# MCU.net
KiCad netlist of a schematic drawn in Altium Designer
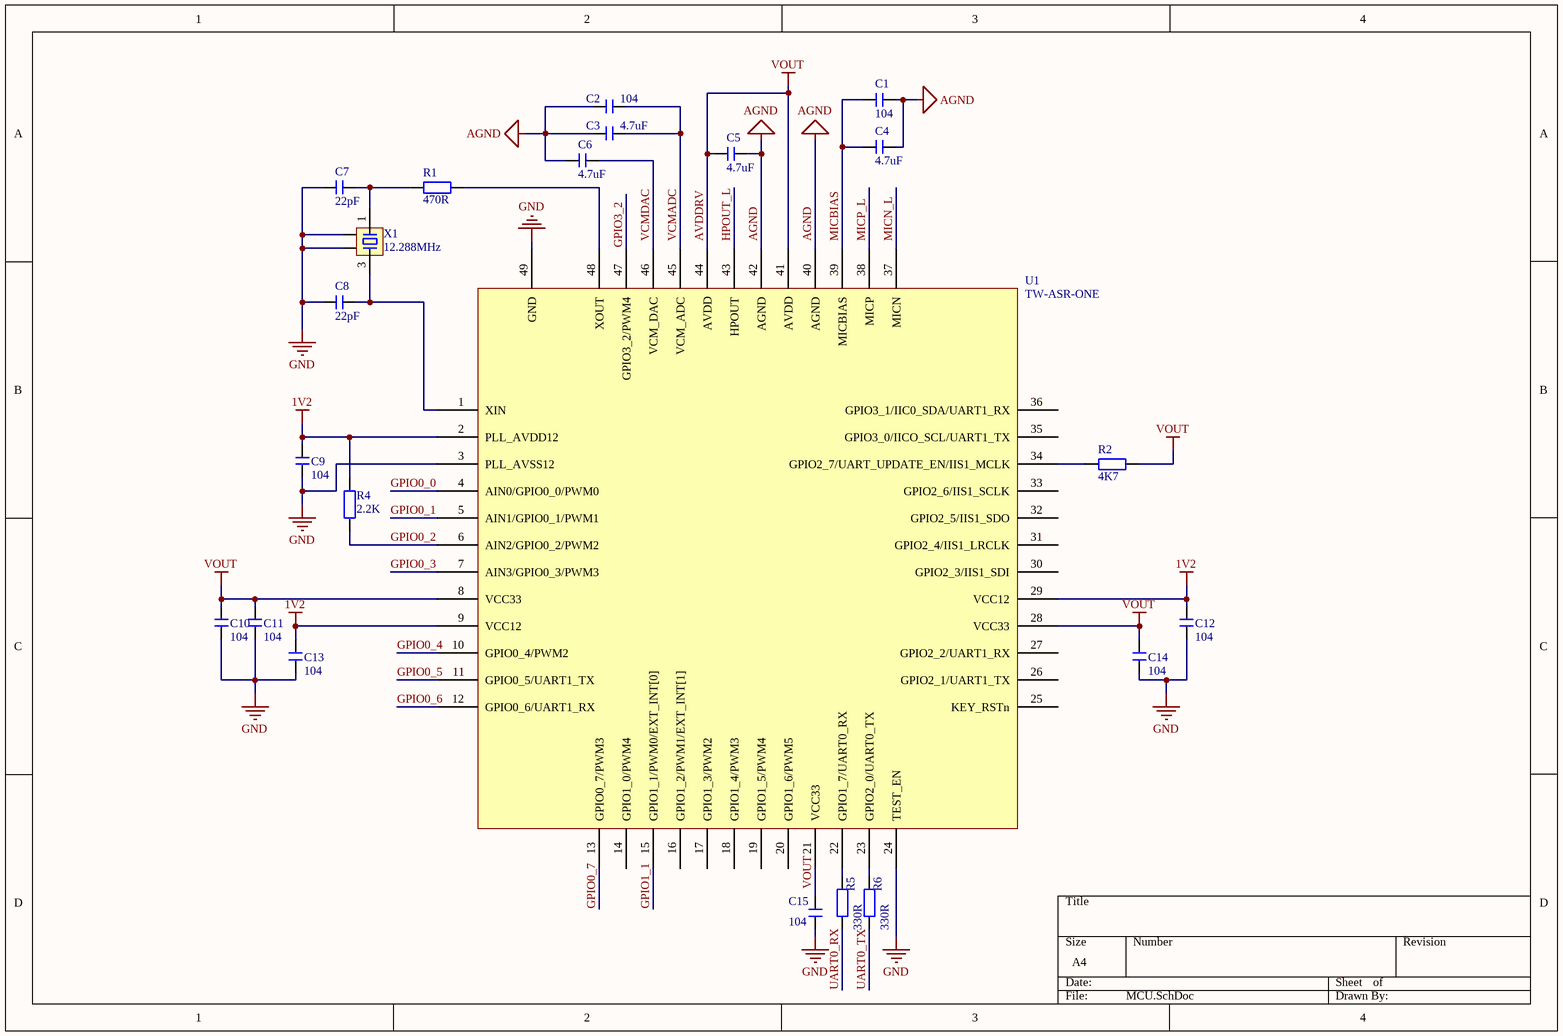
[diagram p0: MCU.SchDoc]

(export (version "E")
  (design (tool "Eeschema 10.0.6"))
  (components
    (comp (ref "C1")
      (value "104")
      (footprint "C 0603_L")
      (description "无极性贴片电容")
      (fields (field (name "版权归属") "源创客"))
      (libsource (lib "3.1   - 电阻-电容-电感") (part "C"))
    )
    (comp (ref "C2")
      (value "104")
      (footprint "C 0603_L")
      (description "无极性贴片电容")
      (fields (field (name "版权归属") "源创客"))
      (libsource (lib "3.1   - 电阻-电容-电感") (part "C"))
    )
    (comp (ref "C3")
      (value "4.7uF")
      (footprint "C 0603_L")
      (description "无极性贴片电容")
      (fields (field (name "版权归属") "源创客"))
      (libsource (lib "3.1   - 电阻-电容-电感") (part "C"))
    )
    (comp (ref "C4")
      (value "4.7uF")
      (footprint "C 0603_L")
      (description "无极性贴片电容")
      (fields (field (name "版权归属") "源创客"))
      (libsource (lib "3.1   - 电阻-电容-电感") (part "C"))
    )
    (comp (ref "C5")
      (value "4.7uF")
      (footprint "C 0603_L")
      (description "无极性贴片电容")
      (fields (field (name "版权归属") "源创客"))
      (libsource (lib "3.1   - 电阻-电容-电感") (part "C"))
    )
    (comp (ref "C6")
      (value "4.7uF")
      (footprint "C 0603_L")
      (description "无极性贴片电容")
      (fields (field (name "版权归属") "源创客"))
      (libsource (lib "3.1   - 电阻-电容-电感") (part "C"))
    )
    (comp (ref "C7")
      (value "22pF")
      (footprint "C 0603_L")
      (description "无极性贴片电容")
      (fields (field (name "版权归属") "源创客"))
      (libsource (lib "3.1   - 电阻-电容-电感") (part "C"))
    )
    (comp (ref "C8")
      (value "22pF")
      (footprint "C 0603_L")
      (description "无极性贴片电容")
      (fields (field (name "版权归属") "源创客"))
      (libsource (lib "3.1   - 电阻-电容-电感") (part "C"))
    )
    (comp (ref "C9")
      (value "104")
      (footprint "C 0603_L")
      (description "无极性贴片电容")
      (fields (field (name "版权归属") "源创客"))
      (libsource (lib "3.1   - 电阻-电容-电感") (part "C"))
    )
    (comp (ref "C10")
      (value "104")
      (footprint "C 0603_L")
      (description "无极性贴片电容")
      (fields (field (name "版权归属") "源创客"))
      (libsource (lib "3.1   - 电阻-电容-电感") (part "C"))
    )
    (comp (ref "C11")
      (value "104")
      (footprint "C 0603_L")
      (description "无极性贴片电容")
      (fields (field (name "版权归属") "源创客"))
      (libsource (lib "3.1   - 电阻-电容-电感") (part "C"))
    )
    (comp (ref "C12")
      (value "104")
      (footprint "C 0603_L")
      (description "无极性贴片电容")
      (fields (field (name "版权归属") "源创客"))
      (libsource (lib "3.1   - 电阻-电容-电感") (part "C"))
    )
    (comp (ref "C13")
      (value "104")
      (footprint "C 0603_L")
      (description "无极性贴片电容")
      (fields (field (name "版权归属") "源创客"))
      (libsource (lib "3.1   - 电阻-电容-电感") (part "C"))
    )
    (comp (ref "C14")
      (value "104")
      (footprint "C 0603_L")
      (description "无极性贴片电容")
      (fields (field (name "版权归属") "源创客"))
      (libsource (lib "3.1   - 电阻-电容-电感") (part "C"))
    )
    (comp (ref "C15")
      (value "104")
      (footprint "C 0603_L")
      (description "无极性贴片电容")
      (fields (field (name "版权归属") "源创客"))
      (libsource (lib "3.1   - 电阻-电容-电感") (part "C"))
    )
    (comp (ref "R1")
      (value "470R")
      (footprint "R 0603_L")
      (description "贴片电阻")
      (fields (field (name "版权归属") "源创客"))
      (libsource (lib "3.1   - 电阻-电容-电感") (part "R"))
    )
    (comp (ref "R2")
      (value "4K7")
      (footprint "R 0603_L")
      (description "贴片电阻")
      (fields (field (name "版权归属") "源创客"))
      (libsource (lib "3.1   - 电阻-电容-电感") (part "R"))
    )
    (comp (ref "R4")
      (value "2.2K")
      (footprint "R 0603_L")
      (description "贴片电阻")
      (fields (field (name "版权归属") "源创客"))
      (libsource (lib "3.1   - 电阻-电容-电感") (part "R"))
    )
    (comp (ref "R5")
      (value "330R")
      (footprint "R 0603_L")
      (description "贴片电阻")
      (fields (field (name "版权归属") "源创客"))
      (libsource (lib "3.1   - 电阻-电容-电感") (part "R"))
    )
    (comp (ref "R6")
      (value "330R")
      (footprint "R 0603_L")
      (description "贴片电阻")
      (fields (field (name "版权归属") "源创客"))
      (libsource (lib "3.1   - 电阻-电容-电感") (part "R"))
    )
    (comp (ref "U1")
      (value "TW-ASR-ONE")
      (footprint "QFN48 6X6")
      (libsource (lib "语音识别和合成模块") (part "TW-ASR-ONE"))
    )
    (comp (ref "X1")
      (value "12.288MHz")
      (footprint "OSC 3225-4P")
      (description "4脚无源晶振")
      (fields (field (name "版权归属") "源创客"))
      (libsource (lib "10.1 - 保险丝-晶振") (part "XTAL-4P"))
    )
  )
  (nets
    (net (code "1") (name "/GPIO0_0") (class "Default")
      (node (ref "U1") (pin "4") (pinfunction "AIN0/GPIO0_0/PWM0_4") (pintype "passive"))
    )
    (net (code "2") (name "/GPIO0_1") (class "Default")
      (node (ref "U1") (pin "5") (pinfunction "AIN1/GPIO0_1/PWM1_5") (pintype "passive"))
    )
    (net (code "3") (name "/GPIO0_2") (class "Default")
      (node (ref "R4") (pin "1") (pinfunction "1_1") (pintype "passive"))
      (node (ref "U1") (pin "6") (pinfunction "AIN2/GPIO0_2/PWM2_6") (pintype "passive"))
    )
    (net (code "4") (name "/GPIO0_3") (class "Default")
      (node (ref "U1") (pin "7") (pinfunction "AIN3/GPIO0_3/PWM3_7") (pintype "passive"))
    )
    (net (code "5") (name "/GPIO0_4") (class "Default")
      (node (ref "U1") (pin "10") (pinfunction "GPIO0_4/PWM2_10") (pintype "passive"))
    )
    (net (code "6") (name "/GPIO0_5") (class "Default")
      (node (ref "U1") (pin "11") (pinfunction "GPIO0_5/UART1_TX_11") (pintype "passive"))
    )
    (net (code "7") (name "/GPIO0_6") (class "Default")
      (node (ref "U1") (pin "12") (pinfunction "GPIO0_6/UART1_RX_12") (pintype "passive"))
    )
    (net (code "8") (name "/GPIO0_7") (class "Default")
      (node (ref "U1") (pin "13") (pinfunction "GPIO0_7/PWM3_13") (pintype "passive"))
    )
    (net (code "9") (name "/GPIO1_1") (class "Default")
      (node (ref "U1") (pin "15") (pinfunction "GPIO1_1/PWM0/EXT_INT[0]_15") (pintype "passive"))
    )
    (net (code "10") (name "/GPIO3_2") (class "Default")
      (node (ref "U1") (pin "47") (pinfunction "GPIO3_2/PWM4_47") (pintype "passive"))
    )
    (net (code "11") (name "/HPOUT_L") (class "Default")
      (node (ref "U1") (pin "43") (pinfunction "HPOUT_43") (pintype "passive"))
    )
    (net (code "12") (name "/MICBIAS") (class "Default")
      (node (ref "C1") (pin "1") (pinfunction "1_1") (pintype "passive"))
      (node (ref "C4") (pin "1") (pinfunction "1_1") (pintype "passive"))
      (node (ref "U1") (pin "39") (pinfunction "MICBIAS_39") (pintype "passive"))
    )
    (net (code "13") (name "/MICN_L") (class "Default")
      (node (ref "U1") (pin "37") (pinfunction "MICN_37") (pintype "passive"))
    )
    (net (code "14") (name "/MICP_L") (class "Default")
      (node (ref "U1") (pin "38") (pinfunction "MICP_38") (pintype "passive"))
    )
    (net (code "15") (name "/UART0_RX") (class "Default")
      (node (ref "R5") (pin "1") (pinfunction "1_1") (pintype "passive"))
    )
    (net (code "16") (name "/UART0_TX") (class "Default")
      (node (ref "R6") (pin "1") (pinfunction "1_1") (pintype "passive"))
    )
    (net (code "17") (name "/VCMADC") (class "Default")
      (node (ref "C2") (pin "2") (pinfunction "2_2") (pintype "passive"))
      (node (ref "C3") (pin "2") (pinfunction "2_2") (pintype "passive"))
      (node (ref "U1") (pin "45") (pinfunction "VCM_ADC_45") (pintype "passive"))
    )
    (net (code "18") (name "/VCMDAC") (class "Default")
      (node (ref "C6") (pin "2") (pinfunction "2_2") (pintype "passive"))
      (node (ref "U1") (pin "46") (pinfunction "VCM_DAC_46") (pintype "passive"))
    )
    (net (code "19") (name "1V2") (class "Default")
      (node (ref "C12") (pin "2") (pinfunction "2_2") (pintype "passive"))
      (node (ref "C13") (pin "2") (pinfunction "2_2") (pintype "passive"))
      (node (ref "C9") (pin "2") (pinfunction "2_2") (pintype "passive"))
      (node (ref "R4") (pin "2") (pinfunction "2_2") (pintype "passive"))
      (node (ref "U1") (pin "2") (pinfunction "PLL_AVDD12_2") (pintype "passive"))
      (node (ref "U1") (pin "29") (pinfunction "VCC12_29") (pintype "passive"))
      (node (ref "U1") (pin "9") (pinfunction "VCC12_9") (pintype "passive"))
    )
    (net (code "20") (name "AGND") (class "Default")
      (node (ref "C1") (pin "2") (pinfunction "2_2") (pintype "passive"))
      (node (ref "C2") (pin "1") (pinfunction "1_1") (pintype "passive"))
      (node (ref "C3") (pin "1") (pinfunction "1_1") (pintype "passive"))
      (node (ref "C4") (pin "2") (pinfunction "2_2") (pintype "passive"))
      (node (ref "C5") (pin "2") (pinfunction "2_2") (pintype "passive"))
      (node (ref "C6") (pin "1") (pinfunction "1_1") (pintype "passive"))
      (node (ref "U1") (pin "40") (pinfunction "AGND_40") (pintype "passive"))
      (node (ref "U1") (pin "42") (pinfunction "AGND_42") (pintype "passive"))
    )
    (net (code "21") (name "GND") (class "Default")
      (node (ref "C10") (pin "1") (pinfunction "1_1") (pintype "passive"))
      (node (ref "C11") (pin "1") (pinfunction "1_1") (pintype "passive"))
      (node (ref "C12") (pin "1") (pinfunction "1_1") (pintype "passive"))
      (node (ref "C13") (pin "1") (pinfunction "1_1") (pintype "passive"))
      (node (ref "C14") (pin "1") (pinfunction "1_1") (pintype "passive"))
      (node (ref "C15") (pin "1") (pinfunction "1_1") (pintype "passive"))
      (node (ref "C7") (pin "1") (pinfunction "1_1") (pintype "passive"))
      (node (ref "C8") (pin "1") (pinfunction "1_1") (pintype "passive"))
      (node (ref "C9") (pin "1") (pinfunction "1_1") (pintype "passive"))
      (node (ref "U1") (pin "24") (pinfunction "TEST_EN_24") (pintype "passive"))
      (node (ref "U1") (pin "3") (pinfunction "PLL_AVSS12_3") (pintype "passive"))
      (node (ref "U1") (pin "49") (pinfunction "GND_49") (pintype "passive"))
      (node (ref "X1") (pin "2") (pinfunction "2_2") (pintype "passive"))
      (node (ref "X1") (pin "4") (pinfunction "4_4") (pintype "passive"))
    )
    (net (code "22") (name "Net-(C7-Pad2)") (class "Default")
      (node (ref "C7") (pin "2") (pinfunction "2_2") (pintype "passive"))
      (node (ref "R1") (pin "1") (pinfunction "1_1") (pintype "passive"))
      (node (ref "X1") (pin "1") (pinfunction "1_1") (pintype "passive"))
    )
    (net (code "23") (name "Net-(U1-GPIO1_7{slash}UART0_RX)") (class "Default")
      (node (ref "R5") (pin "2") (pinfunction "2_2") (pintype "passive"))
      (node (ref "U1") (pin "22") (pinfunction "GPIO1_7/UART0_RX_22") (pintype "passive"))
    )
    (net (code "24") (name "Net-(U1-GPIO2_0{slash}UART0_TX)") (class "Default")
      (node (ref "R6") (pin "2") (pinfunction "2_2") (pintype "passive"))
      (node (ref "U1") (pin "23") (pinfunction "GPIO2_0/UART0_TX_23") (pintype "passive"))
    )
    (net (code "25") (name "Net-(U1-GPIO2_7{slash}UART_UPDATE_EN{slash}IIS1_MCLK)") (class "Default")
      (node (ref "R2") (pin "1") (pinfunction "1_1") (pintype "passive"))
      (node (ref "U1") (pin "34") (pinfunction "GPIO2_7/UART_UPDATE_EN/IIS1_MCLK_34") (pintype "passive"))
    )
    (net (code "26") (name "Net-(U1-XIN)") (class "Default")
      (node (ref "C8") (pin "2") (pinfunction "2_2") (pintype "passive"))
      (node (ref "U1") (pin "1") (pinfunction "XIN_1") (pintype "passive"))
      (node (ref "X1") (pin "3") (pinfunction "3_3") (pintype "passive"))
    )
    (net (code "27") (name "Net-(U1-XOUT)") (class "Default")
      (node (ref "R1") (pin "2") (pinfunction "2_2") (pintype "passive"))
      (node (ref "U1") (pin "48") (pinfunction "XOUT_48") (pintype "passive"))
    )
    (net (code "28") (name "VOUT") (class "Default")
      (node (ref "C10") (pin "2") (pinfunction "2_2") (pintype "passive"))
      (node (ref "C11") (pin "2") (pinfunction "2_2") (pintype "passive"))
      (node (ref "C14") (pin "2") (pinfunction "2_2") (pintype "passive"))
      (node (ref "C15") (pin "2") (pinfunction "2_2") (pintype "passive"))
      (node (ref "C5") (pin "1") (pinfunction "1_1") (pintype "passive"))
      (node (ref "R2") (pin "2") (pinfunction "2_2") (pintype "passive"))
      (node (ref "U1") (pin "21") (pinfunction "VCC33_21") (pintype "passive"))
      (node (ref "U1") (pin "28") (pinfunction "VCC33_28") (pintype "passive"))
      (node (ref "U1") (pin "41") (pinfunction "AVDD_41") (pintype "passive"))
      (node (ref "U1") (pin "44") (pinfunction "AVDD_44") (pintype "passive"))
      (node (ref "U1") (pin "8") (pinfunction "VCC33_8") (pintype "passive"))
    )
    (net (code "29") (name "unconnected-(U1-GPIO1_0{slash}PWM4-Pad14)") (class "Default")
      (node (ref "U1") (pin "14") (pinfunction "GPIO1_0/PWM4_14") (pintype "passive"))
    )
    (net (code "30") (name "unconnected-(U1-GPIO1_2{slash}PWM1{slash}EXT_INT[1]-Pad16)") (class "Default")
      (node (ref "U1") (pin "16") (pinfunction "GPIO1_2/PWM1/EXT_INT[1]_16") (pintype "passive"))
    )
    (net (code "31") (name "unconnected-(U1-GPIO1_3{slash}PWM2-Pad17)") (class "Default")
      (node (ref "U1") (pin "17") (pinfunction "GPIO1_3/PWM2_17") (pintype "passive"))
    )
    (net (code "32") (name "unconnected-(U1-GPIO1_4{slash}PWM3-Pad18)") (class "Default")
      (node (ref "U1") (pin "18") (pinfunction "GPIO1_4/PWM3_18") (pintype "passive"))
    )
    (net (code "33") (name "unconnected-(U1-GPIO1_5{slash}PWM4-Pad19)") (class "Default")
      (node (ref "U1") (pin "19") (pinfunction "GPIO1_5/PWM4_19") (pintype "passive"))
    )
    (net (code "34") (name "unconnected-(U1-GPIO1_6{slash}PWM5-Pad20)") (class "Default")
      (node (ref "U1") (pin "20") (pinfunction "GPIO1_6/PWM5_20") (pintype "passive"))
    )
    (net (code "35") (name "unconnected-(U1-GPIO2_1{slash}UART1_TX-Pad26)") (class "Default")
      (node (ref "U1") (pin "26") (pinfunction "GPIO2_1/UART1_TX_26") (pintype "passive"))
    )
    (net (code "36") (name "unconnected-(U1-GPIO2_2{slash}UART1_RX-Pad27)") (class "Default")
      (node (ref "U1") (pin "27") (pinfunction "GPIO2_2/UART1_RX_27") (pintype "passive"))
    )
    (net (code "37") (name "unconnected-(U1-GPIO2_3{slash}IIS1_SDI-Pad30)") (class "Default")
      (node (ref "U1") (pin "30") (pinfunction "GPIO2_3/IIS1_SDI_30") (pintype "passive"))
    )
    (net (code "38") (name "unconnected-(U1-GPIO2_4{slash}IIS1_LRCLK-Pad31)") (class "Default")
      (node (ref "U1") (pin "31") (pinfunction "GPIO2_4/IIS1_LRCLK_31") (pintype "passive"))
    )
    (net (code "39") (name "unconnected-(U1-GPIO2_5{slash}IIS1_SDO-Pad32)") (class "Default")
      (node (ref "U1") (pin "32") (pinfunction "GPIO2_5/IIS1_SDO_32") (pintype "passive"))
    )
    (net (code "40") (name "unconnected-(U1-GPIO2_6{slash}IIS1_SCLK-Pad33)") (class "Default")
      (node (ref "U1") (pin "33") (pinfunction "GPIO2_6/IIS1_SCLK_33") (pintype "passive"))
    )
    (net (code "41") (name "unconnected-(U1-GPIO3_0{slash}IICO_SCL{slash}UART1_TX-Pad35)") (class "Default")
      (node (ref "U1") (pin "35") (pinfunction "GPIO3_0/IICO_SCL/UART1_TX_35") (pintype "passive"))
    )
    (net (code "42") (name "unconnected-(U1-GPIO3_1{slash}IIC0_SDA{slash}UART1_RX-Pad36)") (class "Default")
      (node (ref "U1") (pin "36") (pinfunction "GPIO3_1/IIC0_SDA/UART1_RX_36") (pintype "passive"))
    )
    (net (code "43") (name "unconnected-(U1-KEY_RSTn-Pad25)") (class "Default")
      (node (ref "U1") (pin "25") (pinfunction "KEY_RSTn_25") (pintype "passive"))
    )
  )
)
